# 3yp_node.net
KiCad netlist of a schematic drawn in EAGLE
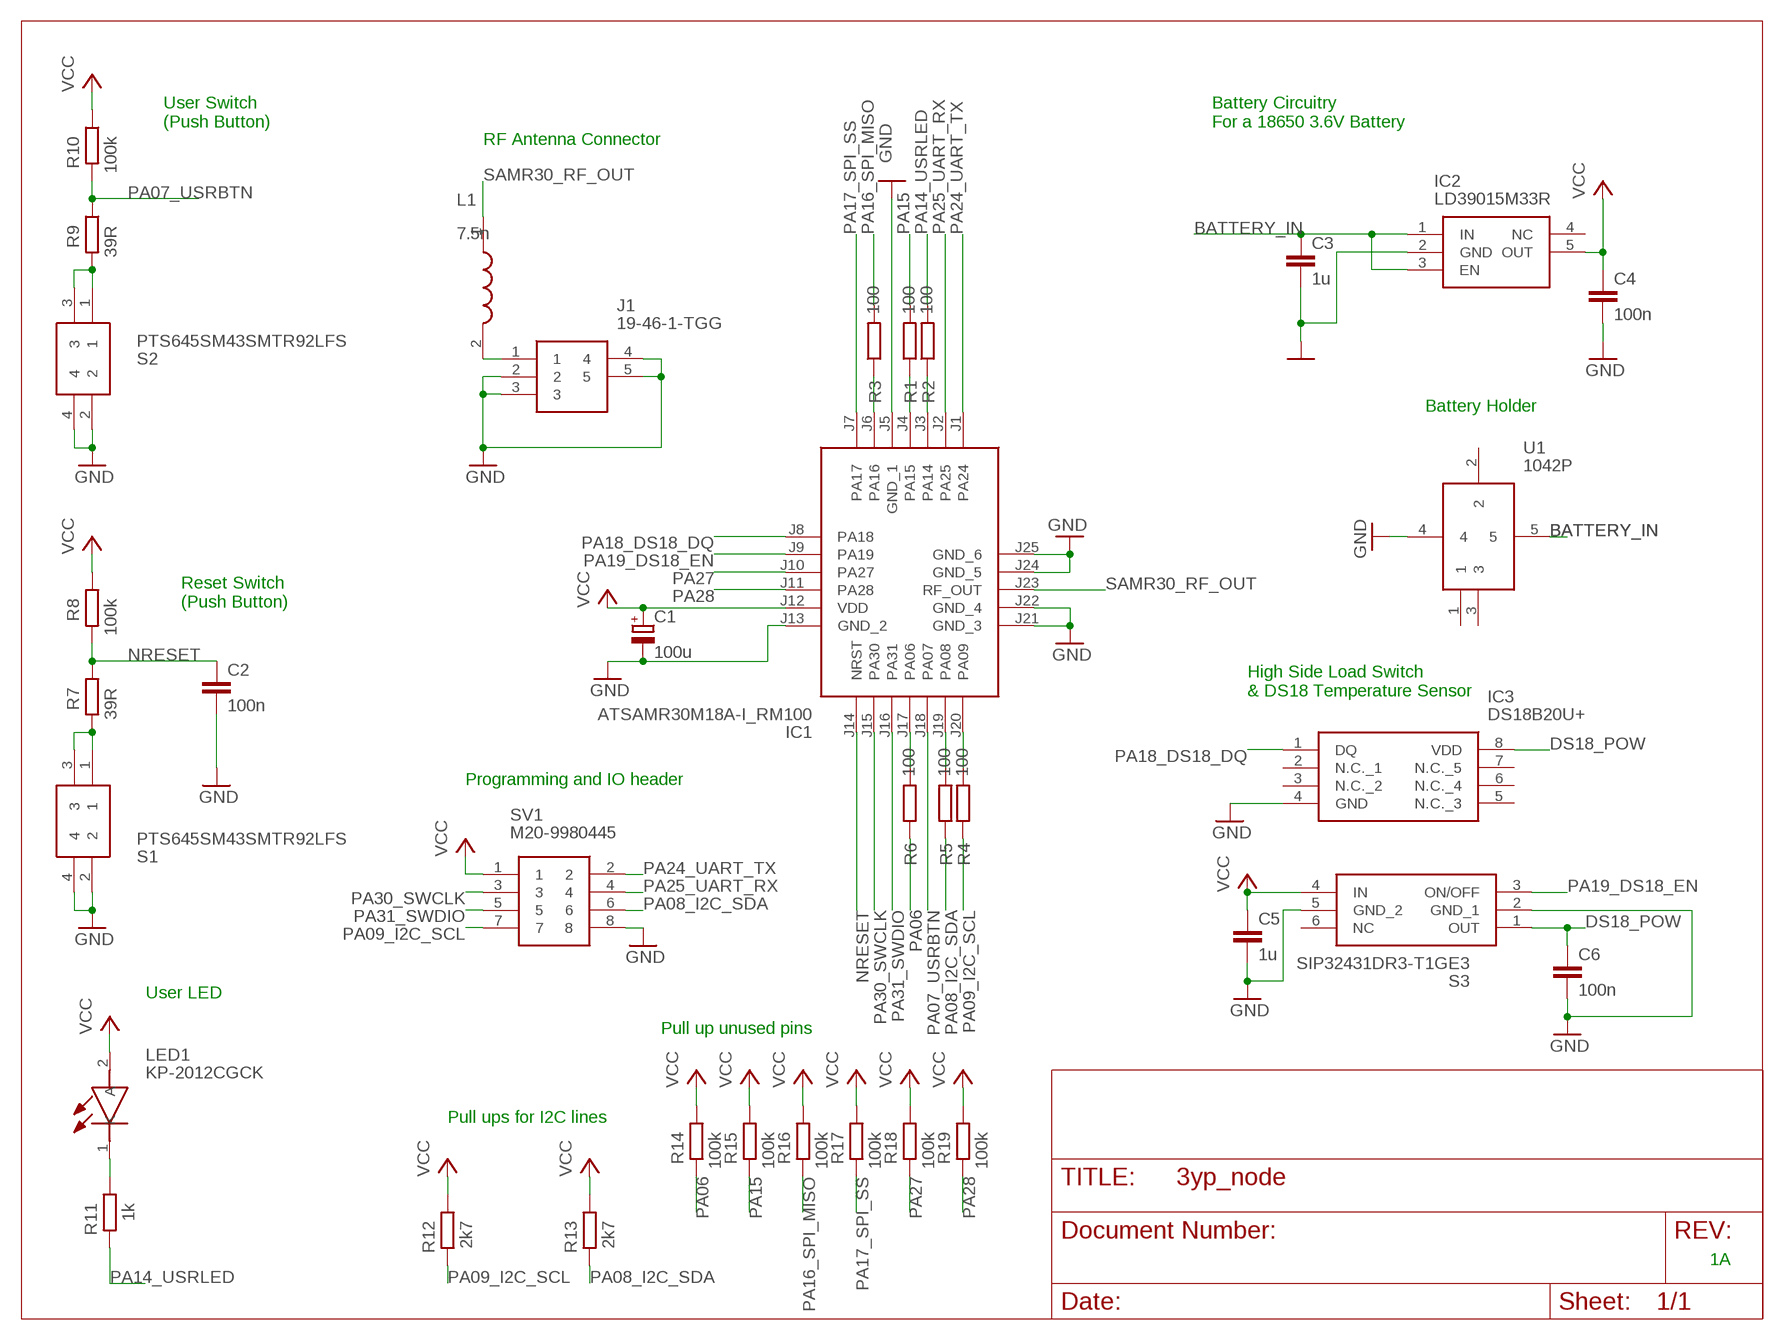
[diagram p0: schematic, sheet 1]

(export (version "E")
  (design (tool "Eeschema 10.0.6"))
  (components
    (comp (ref "C1")
      (value "100u")
      (footprint "eagle-import:A_3216-18W")
      (libsource (lib "eagle-import") (part "CPOL-EUA/3216-18W"))
    )
    (comp (ref "C2")
      (value "100n")
      (footprint "eagle-import:C0805")
      (libsource (lib "eagle-import") (part "C-EUC0805"))
    )
    (comp (ref "C3")
      (value "1u")
      (footprint "eagle-import:C0805")
      (libsource (lib "eagle-import") (part "C-EUC0805"))
    )
    (comp (ref "C4")
      (value "100n")
      (footprint "eagle-import:C0805")
      (libsource (lib "eagle-import") (part "C-EUC0805"))
    )
    (comp (ref "C5")
      (value "1u")
      (footprint "eagle-import:C0805")
      (libsource (lib "eagle-import") (part "C-EUC0805"))
    )
    (comp (ref "C6")
      (value "100n")
      (footprint "eagle-import:C0805")
      (libsource (lib "eagle-import") (part "C-EUC0805"))
    )
    (comp (ref "IC1")
      (value "ATSAMR30M18A-I_RM100")
      (footprint "eagle-import:ATSAMR30M18AIRM100")
      (fields
        (field (name "MANUFACTURER_PART_NUMBER") "ATSAMR30M18A-I/RM100")
        (field (name "MOUSER_PART_NUMBER") "556-AMR30M18AIRM100")
        (field (name "RS_PART_NUMBER") "1840450")
      )
      (libsource (lib "eagle-import") (part "ATSAMR30M18A-I_RM100"))
    )
    (comp (ref "IC2")
      (value "LD39015M33R")
      (footprint "eagle-import:SOT95P280X145-5N")
      (fields
        (field (name "MOUSER_PART_NUMBER") "511-LD39015M33R")
        (field (name "RS_PART_NUMBER") "7958965P")
      )
      (libsource (lib "eagle-import") (part "LD39015M33R"))
    )
    (comp (ref "IC3")
      (value "DS18B20U+")
      (footprint "eagle-import:SOP65P490X110-8N")
      (fields (field (name "MOUSER_PART_NUMBER") "700-DS18B20U"))
      (libsource (lib "eagle-import") (part "DS18B20U+"))
    )
    (comp (ref "J1")
      (value "19-46-1-TGG")
      (footprint "eagle-import:19-46-1-TGG_1")
      (libsource (lib "eagle-import") (part "19-46-1-TGG"))
    )
    (comp (ref "L1")
      (value "7.5n")
      (footprint "eagle-import:INDC1006X60N")
      (fields
        (field (name "MANUFACTURER_PART_NUMBER") "MHQ1005P10NJT")
        (field (name "MOUSER_PART_NUMBER") "810-MHQ1005P10NJT")
        (field (name "RS_PART_NUMBER") "7958243P")
      )
      (libsource (lib "eagle-import") (part "MHQ1005P10NJT"))
    )
    (comp (ref "LED1")
      (value "KP-2012CGCK")
      (footprint "eagle-import:LEDC2012X110N")
      (fields (field (name "RS_PART_NUMBER") "8610037P"))
      (libsource (lib "eagle-import") (part "KP-2012CGCK"))
    )
    (comp (ref "R1")
      (value "100")
      (footprint "eagle-import:R0603")
      (libsource (lib "eagle-import") (part "R-EU_R0603"))
    )
    (comp (ref "R2")
      (value "100")
      (footprint "eagle-import:R0603")
      (libsource (lib "eagle-import") (part "R-EU_R0603"))
    )
    (comp (ref "R3")
      (value "100")
      (footprint "eagle-import:R0603")
      (libsource (lib "eagle-import") (part "R-EU_R0603"))
    )
    (comp (ref "R4")
      (value "100")
      (footprint "eagle-import:R0603")
      (libsource (lib "eagle-import") (part "R-EU_R0603"))
    )
    (comp (ref "R5")
      (value "100")
      (footprint "eagle-import:R0603")
      (libsource (lib "eagle-import") (part "R-EU_R0603"))
    )
    (comp (ref "R6")
      (value "100")
      (footprint "eagle-import:R0603")
      (libsource (lib "eagle-import") (part "R-EU_R0603"))
    )
    (comp (ref "R7")
      (value "39R")
      (footprint "eagle-import:R0603")
      (libsource (lib "eagle-import") (part "R-EU_R0603"))
    )
    (comp (ref "R8")
      (value "100k")
      (footprint "eagle-import:R0603")
      (libsource (lib "eagle-import") (part "R-EU_R0603"))
    )
    (comp (ref "R9")
      (value "39R")
      (footprint "eagle-import:R0603")
      (libsource (lib "eagle-import") (part "R-EU_R0603"))
    )
    (comp (ref "R10")
      (value "100k")
      (footprint "eagle-import:R0603")
      (libsource (lib "eagle-import") (part "R-EU_R0603"))
    )
    (comp (ref "R11")
      (value "1k")
      (footprint "eagle-import:R0603")
      (libsource (lib "eagle-import") (part "R-EU_R0603"))
    )
    (comp (ref "R12")
      (value "2k7")
      (footprint "eagle-import:R0603")
      (libsource (lib "eagle-import") (part "R-EU_R0603"))
    )
    (comp (ref "R13")
      (value "2k7")
      (footprint "eagle-import:R0603")
      (libsource (lib "eagle-import") (part "R-EU_R0603"))
    )
    (comp (ref "R14")
      (value "100k")
      (footprint "eagle-import:R0603")
      (libsource (lib "eagle-import") (part "R-EU_R0603"))
    )
    (comp (ref "R15")
      (value "100k")
      (footprint "eagle-import:R0603")
      (libsource (lib "eagle-import") (part "R-EU_R0603"))
    )
    (comp (ref "R16")
      (value "100k")
      (footprint "eagle-import:R0603")
      (libsource (lib "eagle-import") (part "R-EU_R0603"))
    )
    (comp (ref "R17")
      (value "100k")
      (footprint "eagle-import:R0603")
      (libsource (lib "eagle-import") (part "R-EU_R0603"))
    )
    (comp (ref "R18")
      (value "100k")
      (footprint "eagle-import:R0603")
      (libsource (lib "eagle-import") (part "R-EU_R0603"))
    )
    (comp (ref "R19")
      (value "100k")
      (footprint "eagle-import:R0603")
      (libsource (lib "eagle-import") (part "R-EU_R0603"))
    )
    (comp (ref "S1")
      (value "PTS645SM43SMTR92LFS")
      (footprint "eagle-import:PTS645(SMT)")
      (fields (field (name "MOUSER_PART_NUMBER") "611-PTS645SM43SMTR92"))
      (libsource (lib "eagle-import") (part "PTS645SM43SMTR92LFS"))
    )
    (comp (ref "S2")
      (value "PTS645SM43SMTR92LFS")
      (footprint "eagle-import:PTS645(SMT)")
      (fields (field (name "MOUSER_PART_NUMBER") "611-PTS645SM43SMTR92"))
      (libsource (lib "eagle-import") (part "PTS645SM43SMTR92LFS"))
    )
    (comp (ref "S3")
      (value "SIP32431DR3-T1GE3")
      (footprint "eagle-import:SOT65P210X110-6N")
      (fields
        (field (name "MOUSER_PART_NUMBER") "781-SIP32431DR3-GE3")
        (field (name "RS_PART_NUMBER") "1807353")
      )
      (libsource (lib "eagle-import") (part "SIP32431DR3-T1GE3"))
    )
    (comp (ref "SV1")
      (value "M20-9980445")
      (footprint "eagle-import:HDRV8W64P254_2X4_1016X508X868P")
      (fields
        (field (name "MOUSER_PART_NUMBER") "855-M20-9980445")
        (field (name "RS_PART_NUMBER") "6812941P")
      )
      (libsource (lib "eagle-import") (part "M20-9980445"))
    )
    (comp (ref "U1")
      (value "1042P")
      (footprint "eagle-import:1042P")
      (fields (field (name "MOUSER_PART_NUMBER") "534-1042P"))
      (libsource (lib "eagle-import") (part "1042P"))
    )
  )
  (nets
    (net (code "1") (name "/BATTERY_IN") (class "Default")
      (node (ref "C3") (pin "1") (pinfunction "1_1") (pintype "passive"))
      (node (ref "IC2") (pin "1") (pinfunction "IN_1") (pintype "input"))
      (node (ref "IC2") (pin "3") (pinfunction "EN_3") (pintype "bidirectional"))
      (node (ref "U1") (pin "5") (pinfunction "5_5") (pintype "bidirectional"))
    )
    (net (code "2") (name "/DS18_POW") (class "Default")
      (node (ref "C6") (pin "1") (pinfunction "1_1") (pintype "passive"))
      (node (ref "IC3") (pin "8") (pinfunction "VDD_8") (pintype "power_in"))
      (node (ref "S3") (pin "1") (pinfunction "OUT_1") (pintype "bidirectional"))
    )
    (net (code "3") (name "/NRESET") (class "Default")
      (node (ref "C2") (pin "1") (pinfunction "1_1") (pintype "passive"))
      (node (ref "IC1") (pin "J14") (pinfunction "NRST_J14") (pintype "bidirectional"))
      (node (ref "R7") (pin "1") (pinfunction "1_1") (pintype "passive"))
      (node (ref "R8") (pin "2") (pinfunction "2_2") (pintype "passive"))
    )
    (net (code "4") (name "/PA06") (class "Default")
      (node (ref "R14") (pin "2") (pinfunction "2_2") (pintype "passive"))
      (node (ref "R6") (pin "1") (pinfunction "1_1") (pintype "passive"))
    )
    (net (code "5") (name "/PA07_USRBTN") (class "Default")
      (node (ref "IC1") (pin "J18") (pinfunction "PA07_J18") (pintype "bidirectional"))
      (node (ref "R10") (pin "2") (pinfunction "2_2") (pintype "passive"))
      (node (ref "R9") (pin "1") (pinfunction "1_1") (pintype "passive"))
    )
    (net (code "6") (name "/PA08_I2C_SDA") (class "Default")
      (node (ref "R13") (pin "2") (pinfunction "2_2") (pintype "passive"))
      (node (ref "R5") (pin "1") (pinfunction "1_1") (pintype "passive"))
      (node (ref "SV1") (pin "6") (pinfunction "6_6") (pintype "bidirectional"))
    )
    (net (code "7") (name "/PA09_I2C_SCL") (class "Default")
      (node (ref "R12") (pin "2") (pinfunction "2_2") (pintype "passive"))
      (node (ref "R4") (pin "1") (pinfunction "1_1") (pintype "passive"))
      (node (ref "SV1") (pin "7") (pinfunction "7_7") (pintype "bidirectional"))
    )
    (net (code "8") (name "/PA14_USRLED") (class "Default")
      (node (ref "R11") (pin "2") (pinfunction "2_2") (pintype "passive"))
      (node (ref "R2") (pin "2") (pinfunction "2_2") (pintype "passive"))
    )
    (net (code "9") (name "/PA15") (class "Default")
      (node (ref "R1") (pin "2") (pinfunction "2_2") (pintype "passive"))
      (node (ref "R15") (pin "2") (pinfunction "2_2") (pintype "passive"))
    )
    (net (code "10") (name "/PA16_SPI_MISO") (class "Default")
      (node (ref "R16") (pin "2") (pinfunction "2_2") (pintype "passive"))
      (node (ref "R3") (pin "2") (pinfunction "2_2") (pintype "passive"))
    )
    (net (code "11") (name "/PA17_SPI_SS") (class "Default")
      (node (ref "IC1") (pin "J7") (pinfunction "PA17_J7") (pintype "bidirectional"))
      (node (ref "R17") (pin "2") (pinfunction "2_2") (pintype "passive"))
    )
    (net (code "12") (name "/PA18_DS18_DQ") (class "Default")
      (node (ref "IC1") (pin "J8") (pinfunction "PA18_J8") (pintype "bidirectional"))
      (node (ref "IC3") (pin "1") (pinfunction "DQ_1") (pintype "bidirectional"))
    )
    (net (code "13") (name "/PA19_DS18_EN") (class "Default")
      (node (ref "IC1") (pin "J9") (pinfunction "PA19_J9") (pintype "bidirectional"))
      (node (ref "S3") (pin "3") (pinfunction "ON/OFF_3") (pintype "bidirectional"))
    )
    (net (code "14") (name "/PA24_UART_TX") (class "Default")
      (node (ref "IC1") (pin "J1") (pinfunction "PA24_J1") (pintype "bidirectional"))
      (node (ref "SV1") (pin "2") (pinfunction "2_2") (pintype "bidirectional"))
    )
    (net (code "15") (name "/PA25_UART_RX") (class "Default")
      (node (ref "IC1") (pin "J2") (pinfunction "PA25_J2") (pintype "bidirectional"))
      (node (ref "SV1") (pin "4") (pinfunction "4_4") (pintype "bidirectional"))
    )
    (net (code "16") (name "/PA27") (class "Default")
      (node (ref "IC1") (pin "J10") (pinfunction "PA27_J10") (pintype "bidirectional"))
      (node (ref "R18") (pin "2") (pinfunction "2_2") (pintype "passive"))
    )
    (net (code "17") (name "/PA28") (class "Default")
      (node (ref "IC1") (pin "J11") (pinfunction "PA28_J11") (pintype "bidirectional"))
      (node (ref "R19") (pin "2") (pinfunction "2_2") (pintype "passive"))
    )
    (net (code "18") (name "/PA30_SWCLK") (class "Default")
      (node (ref "IC1") (pin "J15") (pinfunction "PA30_J15") (pintype "bidirectional"))
      (node (ref "SV1") (pin "3") (pinfunction "3_3") (pintype "bidirectional"))
    )
    (net (code "19") (name "/PA31_SWDIO") (class "Default")
      (node (ref "IC1") (pin "J16") (pinfunction "PA31_J16") (pintype "bidirectional"))
      (node (ref "SV1") (pin "5") (pinfunction "5_5") (pintype "bidirectional"))
    )
    (net (code "20") (name "/SAMR30_RF_OUT") (class "Default")
      (node (ref "IC1") (pin "J23") (pinfunction "RF_OUT_J23") (pintype "bidirectional"))
      (node (ref "L1") (pin "1") (pinfunction "1_1") (pintype "bidirectional"))
    )
    (net (code "21") (name "GND") (class "Default")
      (node (ref "C1") (pin "-") (pinfunction "-_-") (pintype "passive"))
      (node (ref "C2") (pin "2") (pinfunction "2_2") (pintype "passive"))
      (node (ref "C3") (pin "2") (pinfunction "2_2") (pintype "passive"))
      (node (ref "C4") (pin "2") (pinfunction "2_2") (pintype "passive"))
      (node (ref "C5") (pin "2") (pinfunction "2_2") (pintype "passive"))
      (node (ref "C6") (pin "2") (pinfunction "2_2") (pintype "passive"))
      (node (ref "IC1") (pin "J13") (pinfunction "GND_2_J13") (pintype "bidirectional"))
      (node (ref "IC1") (pin "J21") (pinfunction "GND_3_J21") (pintype "bidirectional"))
      (node (ref "IC1") (pin "J22") (pinfunction "GND_4_J22") (pintype "bidirectional"))
      (node (ref "IC1") (pin "J24") (pinfunction "GND_5_J24") (pintype "bidirectional"))
      (node (ref "IC1") (pin "J25") (pinfunction "GND_6_J25") (pintype "bidirectional"))
      (node (ref "IC1") (pin "J5") (pinfunction "GND_1_J5") (pintype "bidirectional"))
      (node (ref "IC2") (pin "2") (pinfunction "GND_2") (pintype "power_in"))
      (node (ref "IC3") (pin "4") (pinfunction "GND_4") (pintype "power_in"))
      (node (ref "J1") (pin "2") (pinfunction "2_2") (pintype "bidirectional"))
      (node (ref "J1") (pin "3") (pinfunction "3_3") (pintype "bidirectional"))
      (node (ref "J1") (pin "4") (pinfunction "4_4") (pintype "bidirectional"))
      (node (ref "J1") (pin "5") (pinfunction "5_5") (pintype "bidirectional"))
      (node (ref "S1") (pin "2") (pinfunction "2_2") (pintype "bidirectional"))
      (node (ref "S1") (pin "4") (pinfunction "4_4") (pintype "bidirectional"))
      (node (ref "S2") (pin "2") (pinfunction "2_2") (pintype "bidirectional"))
      (node (ref "S2") (pin "4") (pinfunction "4_4") (pintype "bidirectional"))
      (node (ref "S3") (pin "2") (pinfunction "GND_1_2") (pintype "bidirectional"))
      (node (ref "S3") (pin "5") (pinfunction "GND_2_5") (pintype "bidirectional"))
      (node (ref "SV1") (pin "8") (pinfunction "8_8") (pintype "bidirectional"))
      (node (ref "U1") (pin "4") (pinfunction "4_4") (pintype "bidirectional"))
    )
    (net (code "22") (name "Net-(IC1-PA06)") (class "Default")
      (node (ref "IC1") (pin "J17") (pinfunction "PA06_J17") (pintype "bidirectional"))
      (node (ref "R6") (pin "2") (pinfunction "2_2") (pintype "passive"))
    )
    (net (code "23") (name "Net-(IC1-PA08)") (class "Default")
      (node (ref "IC1") (pin "J19") (pinfunction "PA08_J19") (pintype "bidirectional"))
      (node (ref "R5") (pin "2") (pinfunction "2_2") (pintype "passive"))
    )
    (net (code "24") (name "Net-(IC1-PA09)") (class "Default")
      (node (ref "IC1") (pin "J20") (pinfunction "PA09_J20") (pintype "bidirectional"))
      (node (ref "R4") (pin "2") (pinfunction "2_2") (pintype "passive"))
    )
    (net (code "25") (name "Net-(IC1-PA14)") (class "Default")
      (node (ref "IC1") (pin "J3") (pinfunction "PA14_J3") (pintype "bidirectional"))
      (node (ref "R2") (pin "1") (pinfunction "1_1") (pintype "passive"))
    )
    (net (code "26") (name "Net-(IC1-PA15)") (class "Default")
      (node (ref "IC1") (pin "J4") (pinfunction "PA15_J4") (pintype "bidirectional"))
      (node (ref "R1") (pin "1") (pinfunction "1_1") (pintype "passive"))
    )
    (net (code "27") (name "Net-(IC1-PA16)") (class "Default")
      (node (ref "IC1") (pin "J6") (pinfunction "PA16_J6") (pintype "bidirectional"))
      (node (ref "R3") (pin "1") (pinfunction "1_1") (pintype "passive"))
    )
    (net (code "28") (name "Net-(J1-Pad1)") (class "Default")
      (node (ref "J1") (pin "1") (pinfunction "1_1") (pintype "bidirectional"))
      (node (ref "L1") (pin "2") (pinfunction "2_2") (pintype "bidirectional"))
    )
    (net (code "29") (name "Net-(LED1-K)") (class "Default")
      (node (ref "LED1") (pin "1") (pinfunction "K_1") (pintype "bidirectional"))
      (node (ref "R11") (pin "1") (pinfunction "1_1") (pintype "passive"))
    )
    (net (code "30") (name "Net-(R7-Pad2)") (class "Default")
      (node (ref "R7") (pin "2") (pinfunction "2_2") (pintype "passive"))
      (node (ref "S1") (pin "1") (pinfunction "1_1") (pintype "bidirectional"))
      (node (ref "S1") (pin "3") (pinfunction "3_3") (pintype "bidirectional"))
    )
    (net (code "31") (name "Net-(R9-Pad2)") (class "Default")
      (node (ref "R9") (pin "2") (pinfunction "2_2") (pintype "passive"))
      (node (ref "S2") (pin "1") (pinfunction "1_1") (pintype "bidirectional"))
      (node (ref "S2") (pin "3") (pinfunction "3_3") (pintype "bidirectional"))
    )
    (net (code "32") (name "VCC") (class "Default")
      (node (ref "C1") (pin "+") (pinfunction "+_+") (pintype "passive"))
      (node (ref "C4") (pin "1") (pinfunction "1_1") (pintype "passive"))
      (node (ref "C5") (pin "1") (pinfunction "1_1") (pintype "passive"))
      (node (ref "IC1") (pin "J12") (pinfunction "VDD_J12") (pintype "bidirectional"))
      (node (ref "IC2") (pin "5") (pinfunction "OUT_5") (pintype "power_in"))
      (node (ref "LED1") (pin "2") (pinfunction "A_2") (pintype "bidirectional"))
      (node (ref "R10") (pin "1") (pinfunction "1_1") (pintype "passive"))
      (node (ref "R12") (pin "1") (pinfunction "1_1") (pintype "passive"))
      (node (ref "R13") (pin "1") (pinfunction "1_1") (pintype "passive"))
      (node (ref "R14") (pin "1") (pinfunction "1_1") (pintype "passive"))
      (node (ref "R15") (pin "1") (pinfunction "1_1") (pintype "passive"))
      (node (ref "R16") (pin "1") (pinfunction "1_1") (pintype "passive"))
      (node (ref "R17") (pin "1") (pinfunction "1_1") (pintype "passive"))
      (node (ref "R18") (pin "1") (pinfunction "1_1") (pintype "passive"))
      (node (ref "R19") (pin "1") (pinfunction "1_1") (pintype "passive"))
      (node (ref "R8") (pin "1") (pinfunction "1_1") (pintype "passive"))
      (node (ref "S3") (pin "4") (pinfunction "IN_4") (pintype "bidirectional"))
      (node (ref "SV1") (pin "1") (pinfunction "1_1") (pintype "bidirectional"))
    )
    (net (code "33") (name "unconnected-(IC2-NC-Pad4)") (class "Default")
      (node (ref "IC2") (pin "4") (pinfunction "NC_4") (pintype "no_connect"))
    )
    (net (code "34") (name "unconnected-(IC3-N.C._1-Pad2)") (class "Default")
      (node (ref "IC3") (pin "2") (pinfunction "N.C._1_2") (pintype "bidirectional"))
    )
    (net (code "35") (name "unconnected-(IC3-N.C._2-Pad3)") (class "Default")
      (node (ref "IC3") (pin "3") (pinfunction "N.C._2_3") (pintype "bidirectional"))
    )
    (net (code "36") (name "unconnected-(IC3-N.C._3-Pad5)") (class "Default")
      (node (ref "IC3") (pin "5") (pinfunction "N.C._3_5") (pintype "bidirectional"))
    )
    (net (code "37") (name "unconnected-(IC3-N.C._4-Pad6)") (class "Default")
      (node (ref "IC3") (pin "6") (pinfunction "N.C._4_6") (pintype "bidirectional"))
    )
    (net (code "38") (name "unconnected-(IC3-N.C._5-Pad7)") (class "Default")
      (node (ref "IC3") (pin "7") (pinfunction "N.C._5_7") (pintype "bidirectional"))
    )
    (net (code "39") (name "unconnected-(S3-NC-Pad6)") (class "Default")
      (node (ref "S3") (pin "6") (pinfunction "NC_6") (pintype "no_connect"))
    )
    (net (code "40") (name "unconnected-(U1-Pad1)") (class "Default")
      (node (ref "U1") (pin "1") (pinfunction "1_1") (pintype "bidirectional"))
    )
    (net (code "41") (name "unconnected-(U1-Pad2)") (class "Default")
      (node (ref "U1") (pin "2") (pinfunction "2_2") (pintype "bidirectional"))
    )
    (net (code "42") (name "unconnected-(U1-Pad3)") (class "Default")
      (node (ref "U1") (pin "3") (pinfunction "3_3") (pintype "bidirectional"))
    )
  )
)
